# P1DuRFIDBreakout.net
KiCad netlist of a schematic drawn in EAGLE
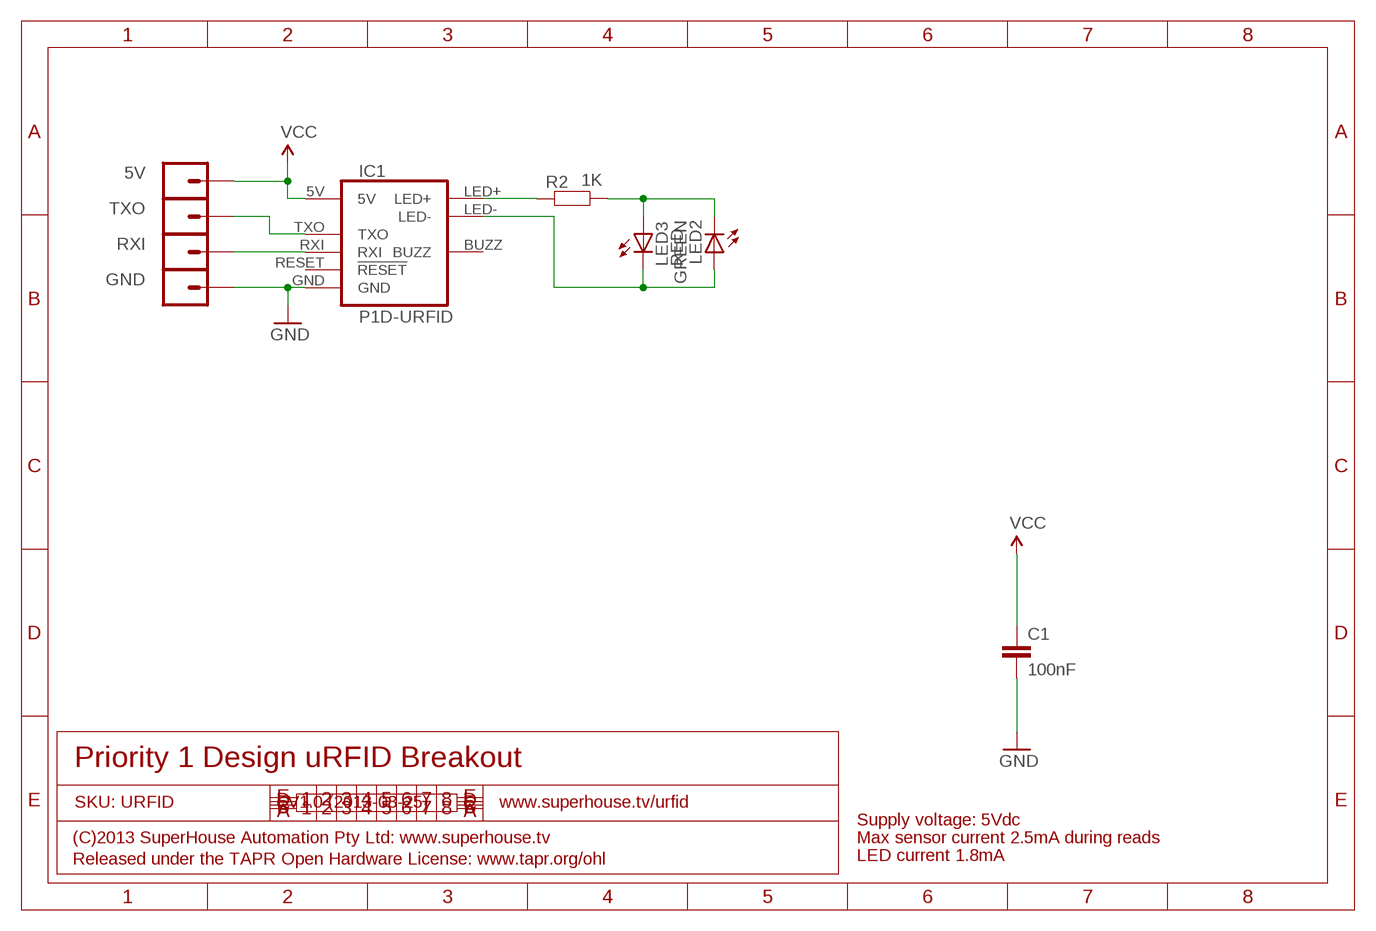
[diagram p0: schematic, sheet 1]

(export (version "E")
  (design (tool "Eeschema 10.0.6"))
  (components
    (comp (ref "5V")
      (value "M01PTH")
      (footprint "eagle-import:1X01")
      (libsource (lib "eagle-import") (part "M01PTH"))
    )
    (comp (ref "C1")
      (value "100nF")
      (footprint "eagle-import:0603")
      (libsource (lib "eagle-import") (part "CAP0603"))
    )
    (comp (ref "GND")
      (value "M01PTH")
      (footprint "eagle-import:1X01")
      (libsource (lib "eagle-import") (part "M01PTH"))
    )
    (comp (ref "IC1")
      (value "P1D-URFID")
      (footprint "eagle-import:URFID")
      (libsource (lib "eagle-import") (part "P1D-URFID"))
    )
    (comp (ref "LED2")
      (value "GREEN")
      (footprint "eagle-import:LED3MM")
      (libsource (lib "eagle-import") (part "LED3MM"))
    )
    (comp (ref "LED3")
      (value "RED")
      (footprint "eagle-import:LED3MM")
      (libsource (lib "eagle-import") (part "LED3MM"))
    )
    (comp (ref "R2")
      (value "1K")
      (footprint "eagle-import:0603")
      (libsource (lib "eagle-import") (part "RESISTOR0603"))
    )
    (comp (ref "RXI")
      (value "M01PTH")
      (footprint "eagle-import:1X01")
      (libsource (lib "eagle-import") (part "M01PTH"))
    )
    (comp (ref "TXO")
      (value "M01PTH")
      (footprint "eagle-import:1X01")
      (libsource (lib "eagle-import") (part "M01PTH"))
    )
  )
  (nets
    (net (code "1") (name "GND") (class "Default")
      (node (ref "C1") (pin "2") (pinfunction "2_2") (pintype "passive"))
      (node (ref "GND") (pin "1") (pinfunction "1_1") (pintype "passive"))
      (node (ref "IC1") (pin "GND") (pinfunction "GND_GND") (pintype "power_in"))
    )
    (net (code "2") (name "Net-(IC1-PadLED+)") (class "Default")
      (node (ref "IC1") (pin "LED+") (pinfunction "LED+_LED+") (pintype "bidirectional"))
      (node (ref "R2") (pin "2") (pinfunction "2_2") (pintype "passive"))
    )
    (net (code "3") (name "Net-(IC1-PadRXI)") (class "Default")
      (node (ref "IC1") (pin "RXI") (pinfunction "RXI_RXI") (pintype "bidirectional"))
      (node (ref "RXI") (pin "1") (pinfunction "1_1") (pintype "passive"))
    )
    (net (code "4") (name "Net-(IC1-PadTXO)") (class "Default")
      (node (ref "IC1") (pin "TXO") (pinfunction "TXO_TXO") (pintype "bidirectional"))
      (node (ref "TXO") (pin "1") (pinfunction "1_1") (pintype "passive"))
    )
    (net (code "5") (name "Net-(LED2-C)") (class "Default")
      (node (ref "LED2") (pin "K") (pinfunction "C_K") (pintype "passive"))
      (node (ref "LED3") (pin "A") (pinfunction "A_A") (pintype "passive"))
      (node (ref "R2") (pin "1") (pinfunction "1_1") (pintype "passive"))
    )
    (net (code "6") (name "Net-(LED3-C)") (class "Default")
      (node (ref "IC1") (pin "LED-") (pinfunction "LED-_LED-") (pintype "bidirectional"))
      (node (ref "LED2") (pin "A") (pinfunction "A_A") (pintype "passive"))
      (node (ref "LED3") (pin "K") (pinfunction "C_K") (pintype "passive"))
    )
    (net (code "7") (name "VCC") (class "Default")
      (node (ref "5V") (pin "1") (pinfunction "1_1") (pintype "passive"))
      (node (ref "C1") (pin "1") (pinfunction "1_1") (pintype "passive"))
      (node (ref "IC1") (pin "5V") (pinfunction "5V_5V") (pintype "power_in"))
    )
    (net (code "8") (name "unconnected-(IC1-PadBUZZ)") (class "Default")
      (node (ref "IC1") (pin "BUZZ") (pinfunction "BUZZ_BUZZ") (pintype "output"))
    )
    (net (code "9") (name "unconnected-(IC1-~{RESET}-PadRESET)") (class "Default")
      (node (ref "IC1") (pin "RESET") (pinfunction "~{RESET}_RESET") (pintype "input"))
    )
  )
)
